# riffleito-xbee-REVA.net
KiCad netlist of a schematic drawn in EAGLE
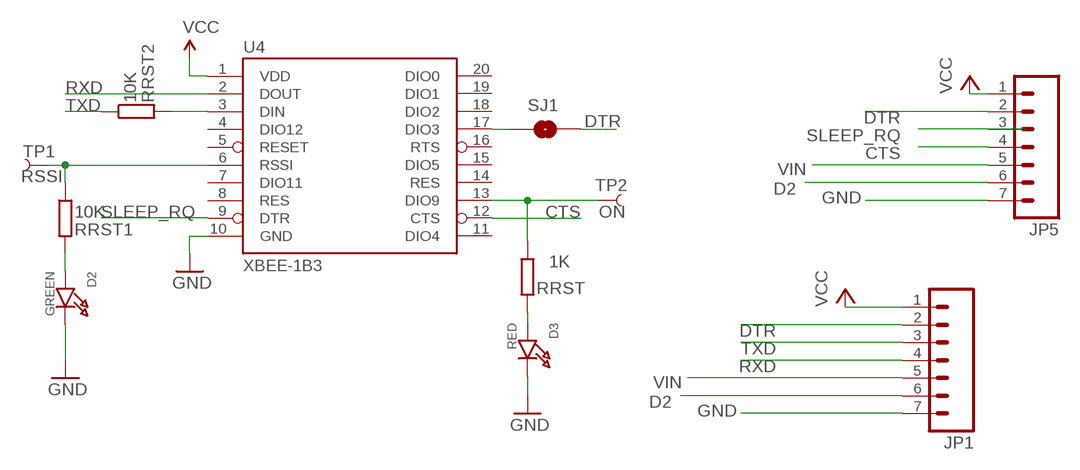
[diagram p0: schematic, sheet 1]

(export (version "E")
  (design (tool "Eeschema 10.0.6"))
  (components
    (comp (ref "D2")
      (value "GREEN")
      (footprint "eagle-import:CHIPLED_0805")
      (libsource (lib "eagle-import") (part "LED0805"))
    )
    (comp (ref "D3")
      (value "RED")
      (footprint "eagle-import:CHIPLED_0805")
      (libsource (lib "eagle-import") (part "LED0805"))
    )
    (comp (ref "JP1")
      (value "M07")
      (footprint "eagle-import:1X07")
      (libsource (lib "eagle-import") (part "M07"))
    )
    (comp (ref "JP5")
      (value "M07")
      (footprint "eagle-import:1X07")
      (libsource (lib "eagle-import") (part "M07"))
    )
    (comp (ref "RRST")
      (value "1K")
      (footprint "eagle-import:R0805")
      (libsource (lib "eagle-import") (part "R-EU_R0805"))
    )
    (comp (ref "RRST1")
      (value "10K")
      (footprint "eagle-import:R0805")
      (libsource (lib "eagle-import") (part "R-EU_R0805"))
    )
    (comp (ref "RRST2")
      (value "10K")
      (footprint "eagle-import:R0805")
      (libsource (lib "eagle-import") (part "R-EU_R0805"))
    )
    (comp (ref "SJ1")
      (value "SOLDERJUMPERNC")
      (footprint "eagle-import:SJ_2S")
      (libsource (lib "eagle-import") (part "SOLDERJUMPERNC"))
    )
    (comp (ref "TP1")
      (value "RSSI")
      (footprint "eagle-import:PAD.03X.05")
      (libsource (lib "eagle-import") (part "TEST-POINT3X5"))
    )
    (comp (ref "TP2")
      (value "ON")
      (footprint "eagle-import:PAD.03X.05")
      (libsource (lib "eagle-import") (part "TEST-POINT3X5"))
    )
    (comp (ref "U4")
      (value "XBEE-1B3")
      (footprint "eagle-import:XBEE-SMD")
      (libsource (lib "eagle-import") (part "XBEE-1B3"))
    )
  )
  (nets
    (net (code "1") (name "/CTS") (class "Default")
      (node (ref "JP5") (pin "4") (pinfunction "4_4") (pintype "passive"))
      (node (ref "U4") (pin "12") (pinfunction "CTS_12") (pintype "output"))
    )
    (net (code "2") (name "/D2") (class "Default")
      (node (ref "JP1") (pin "6") (pinfunction "6_6") (pintype "passive"))
      (node (ref "JP5") (pin "6") (pinfunction "6_6") (pintype "passive"))
    )
    (net (code "3") (name "/DTR") (class "Default")
      (node (ref "JP1") (pin "2") (pinfunction "2_2") (pintype "passive"))
      (node (ref "JP5") (pin "2") (pinfunction "2_2") (pintype "passive"))
      (node (ref "SJ1") (pin "2") (pinfunction "2_2") (pintype "passive"))
    )
    (net (code "4") (name "/RXD") (class "Default")
      (node (ref "JP1") (pin "4") (pinfunction "4_4") (pintype "passive"))
      (node (ref "U4") (pin "2") (pinfunction "DOUT_2") (pintype "output"))
    )
    (net (code "5") (name "/SLEEP_RQ") (class "Default")
      (node (ref "JP5") (pin "3") (pinfunction "3_3") (pintype "passive"))
      (node (ref "U4") (pin "9") (pinfunction "DTR_9") (pintype "bidirectional"))
    )
    (net (code "6") (name "/TXD") (class "Default")
      (node (ref "JP1") (pin "3") (pinfunction "3_3") (pintype "passive"))
      (node (ref "RRST2") (pin "1") (pinfunction "1_1") (pintype "passive"))
    )
    (net (code "7") (name "/VIN") (class "Default")
      (node (ref "JP1") (pin "5") (pinfunction "5_5") (pintype "passive"))
      (node (ref "JP5") (pin "5") (pinfunction "5_5") (pintype "passive"))
    )
    (net (code "8") (name "GND") (class "Default")
      (node (ref "D2") (pin "C") (pinfunction "C_C") (pintype "passive"))
      (node (ref "D3") (pin "C") (pinfunction "C_C") (pintype "passive"))
      (node (ref "JP1") (pin "7") (pinfunction "7_7") (pintype "passive"))
      (node (ref "JP5") (pin "7") (pinfunction "7_7") (pintype "passive"))
      (node (ref "U4") (pin "10") (pinfunction "GND_10") (pintype "power_in"))
    )
    (net (code "9") (name "Net-(D2-PadA)") (class "Default")
      (node (ref "D2") (pin "A") (pinfunction "A_A") (pintype "passive"))
      (node (ref "RRST1") (pin "2") (pinfunction "2_2") (pintype "passive"))
    )
    (net (code "10") (name "Net-(D3-PadA)") (class "Default")
      (node (ref "D3") (pin "A") (pinfunction "A_A") (pintype "passive"))
      (node (ref "RRST") (pin "2") (pinfunction "2_2") (pintype "passive"))
    )
    (net (code "11") (name "Net-(TP1-1)") (class "Default")
      (node (ref "RRST1") (pin "1") (pinfunction "1_1") (pintype "passive"))
      (node (ref "TP1") (pin "P$1") (pinfunction "1_P$1") (pintype "bidirectional"))
      (node (ref "U4") (pin "6") (pinfunction "RSSI_6") (pintype "bidirectional"))
    )
    (net (code "12") (name "Net-(TP2-1)") (class "Default")
      (node (ref "RRST") (pin "1") (pinfunction "1_1") (pintype "passive"))
      (node (ref "TP2") (pin "P$1") (pinfunction "1_P$1") (pintype "bidirectional"))
      (node (ref "U4") (pin "13") (pinfunction "DIO9_13") (pintype "bidirectional"))
    )
    (net (code "13") (name "Net-(U4-DIN)") (class "Default")
      (node (ref "RRST2") (pin "2") (pinfunction "2_2") (pintype "passive"))
      (node (ref "U4") (pin "3") (pinfunction "DIN_3") (pintype "input"))
    )
    (net (code "14") (name "Net-(U4-DIO3)") (class "Default")
      (node (ref "SJ1") (pin "1") (pinfunction "1_1") (pintype "passive"))
      (node (ref "U4") (pin "17") (pinfunction "DIO3_17") (pintype "bidirectional"))
    )
    (net (code "15") (name "VCC") (class "Default")
      (node (ref "JP1") (pin "1") (pinfunction "1_1") (pintype "passive"))
      (node (ref "JP5") (pin "1") (pinfunction "1_1") (pintype "passive"))
      (node (ref "U4") (pin "1") (pinfunction "VDD_1") (pintype "power_in"))
    )
    (net (code "16") (name "unconnected-(U4-DIO0-Pad20)") (class "Default")
      (node (ref "U4") (pin "20") (pinfunction "DIO0_20") (pintype "bidirectional"))
    )
    (net (code "17") (name "unconnected-(U4-DIO1-Pad19)") (class "Default")
      (node (ref "U4") (pin "19") (pinfunction "DIO1_19") (pintype "bidirectional"))
    )
    (net (code "18") (name "unconnected-(U4-DIO2-Pad18)") (class "Default")
      (node (ref "U4") (pin "18") (pinfunction "DIO2_18") (pintype "bidirectional"))
    )
    (net (code "19") (name "unconnected-(U4-DIO4-Pad11)") (class "Default")
      (node (ref "U4") (pin "11") (pinfunction "DIO4_11") (pintype "bidirectional"))
    )
    (net (code "20") (name "unconnected-(U4-DIO5-Pad15)") (class "Default")
      (node (ref "U4") (pin "15") (pinfunction "DIO5_15") (pintype "bidirectional"))
    )
    (net (code "21") (name "unconnected-(U4-DIO11-Pad7)") (class "Default")
      (node (ref "U4") (pin "7") (pinfunction "DIO11_7") (pintype "bidirectional"))
    )
    (net (code "22") (name "unconnected-(U4-DIO12-Pad4)") (class "Default")
      (node (ref "U4") (pin "4") (pinfunction "DIO12_4") (pintype "bidirectional"))
    )
    (net (code "23") (name "unconnected-(U4-RES-Pad8)") (class "Default")
      (node (ref "U4") (pin "8") (pinfunction "RES_8") (pintype "bidirectional"))
    )
    (net (code "24") (name "unconnected-(U4-RES-Pad14)") (class "Default")
      (node (ref "U4") (pin "14") (pinfunction "RES_14") (pintype "bidirectional"))
    )
    (net (code "25") (name "unconnected-(U4-RESET-Pad5)") (class "Default")
      (node (ref "U4") (pin "5") (pinfunction "RESET_5") (pintype "input"))
    )
    (net (code "26") (name "unconnected-(U4-RTS-Pad16)") (class "Default")
      (node (ref "U4") (pin "16") (pinfunction "RTS_16") (pintype "input"))
    )
  )
)
